# Sheet1.net
KiCad netlist of a schematic drawn in Altium Designer
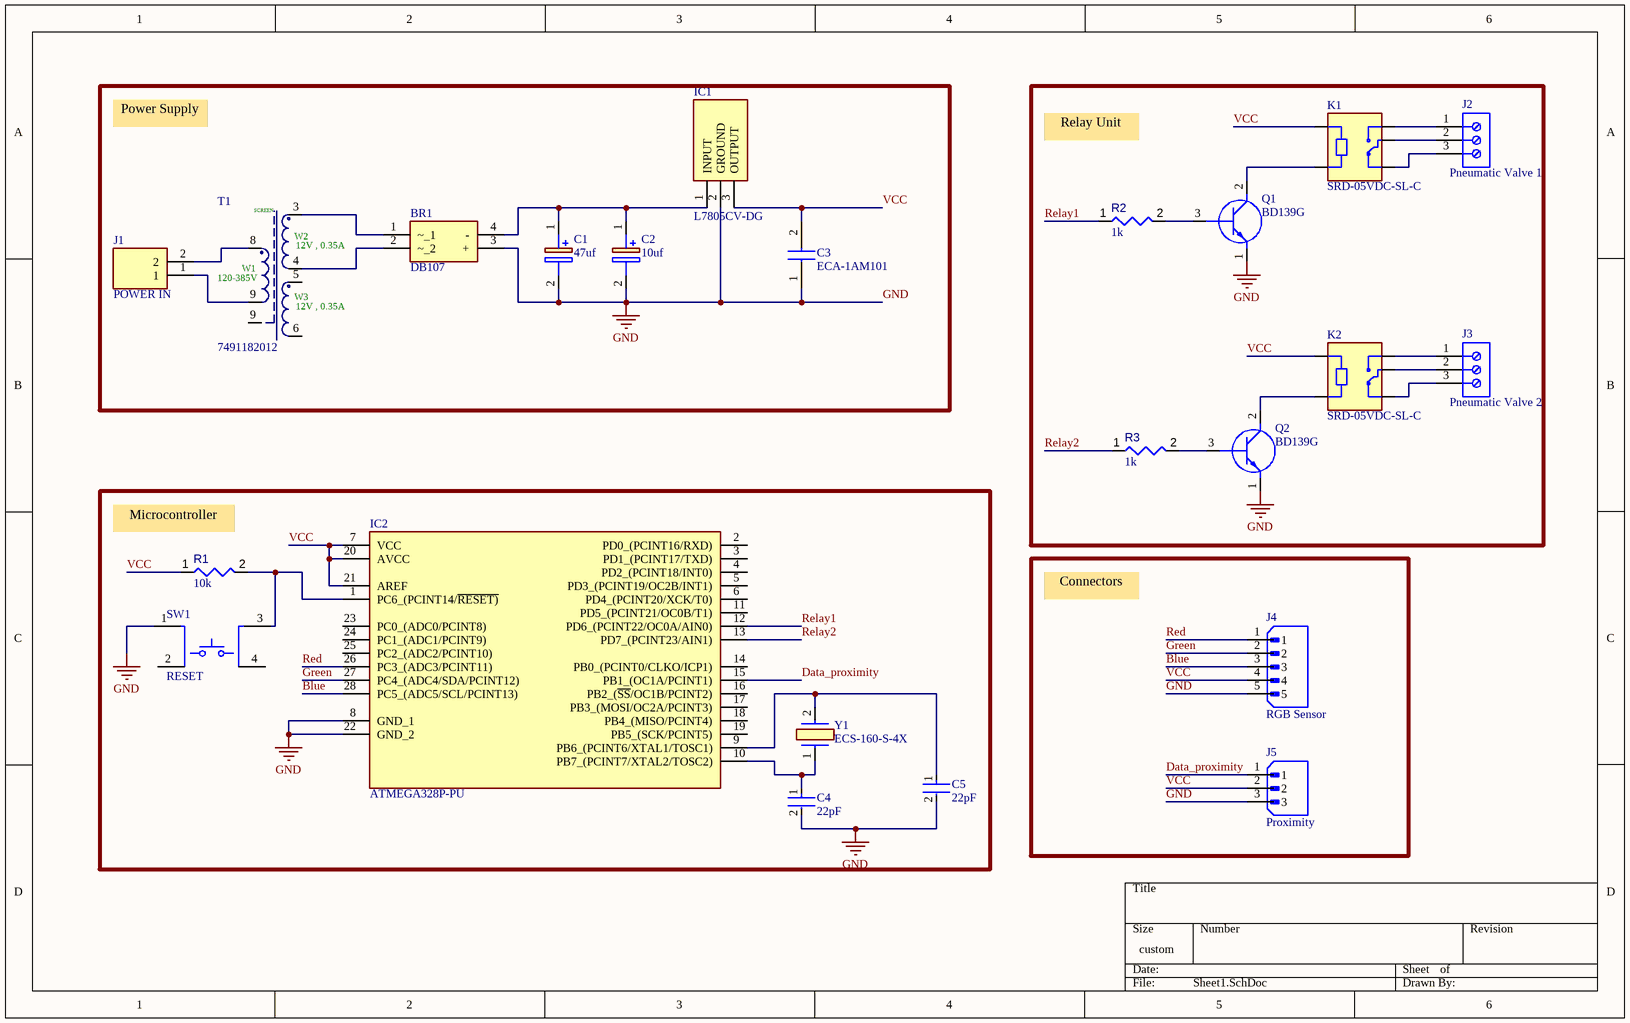
[diagram p0: Sheet1.SchDoc]

(export (version "E")
  (design (tool "Eeschema 10.0.6"))
  (components
    (comp (ref "BR1")
      (value "DB107")
      (footprint "SamacSys:DIP825W50P510L830H340Q4N")
      (description "Bridge Rectifier")
      (fields (field (name "MOUSER PART NUMBER") "583-DB107"))
      (libsource (lib "*") (part "DB107"))
    )
    (comp (ref "C1")
      (value "47uf")
      (footprint "SamacSys:CAPPRD250W55D630H1220")
      (description "Capacitor Polarised")
      (fields
        (field (name "MANUFACTURER_PART_NUMBER") "ECE-A1EN470UB")
        (field (name "MOUSER PART NUMBER") "667-ECE-A1EN470UB")
      )
      (libsource (lib "*") (part "ECE-A1EN470UB"))
    )
    (comp (ref "C2")
      (value "10uf")
      (footprint "SamacSys:CAPPRD200W55D500H1200")
      (description "Capacitor Polarised")
      (fields
        (field (name "MANUFACTURER_PART_NUMBER") "ECA-1EM100")
        (field (name "MOUSER PART NUMBER") "667-ECA-1EM100")
      )
      (libsource (lib "*") (part "ECA-1EM100"))
    )
    (comp (ref "C3")
      (value "ECA-1AM101")
      (footprint "SamacSys:CAPPRD200W55D525H1200")
      (description "Capacitor")
      (fields (field (name "MOUSER PART NUMBER") "667-ECA-1AM101"))
      (libsource (lib "*") (part "ECA-1AM101"))
    )
    (comp (ref "C4")
      (value "22pF")
      (footprint "FP-RCE0DB-MFG")
      (description "Cap Ceramic 22pF 100V C0G ±5% Radial 2.5mm +125°C Ammo Pack")
      (fields (field (name "VOLTAGE") "100V") (field (name "TOLERANCE") "5%"))
      (libsource (lib "Altium Content Vault") (part "b4654b650e69147ec39a6b967a45e02"))
    )
    (comp (ref "C5")
      (value "22pF")
      (footprint "FP-RCE0DB-MFG")
      (description "Cap Ceramic 22pF 100V C0G ±5% Radial 2.5mm +125°C Ammo Pack")
      (fields (field (name "VOLTAGE") "100V") (field (name "TOLERANCE") "5%"))
      (libsource (lib "Altium Content Vault") (part "b4654b650e69147ec39a6b967a45e02"))
    )
    (comp (ref "IC1")
      (value "L7805CV-DG")
      (footprint "SamacSys:TO255P460X1020X2008-3P")
      (description "Integrated Circuit")
      (fields (field (name "MOUSER PART NUMBER") "511-L7805CV-DG"))
      (libsource (lib "*") (part "L7805CV-DG"))
    )
    (comp (ref "IC2")
      (value "ATMEGA328P-PU")
      (footprint "SamacSys:DIP794W53P254L3467H457Q28N")
      (description "Integrated Circuit")
      (fields (field (name "MOUSER PART NUMBER") "556-ATMEGA328P-PU"))
      (libsource (lib "*") (part "ATMEGA328P-PU"))
    )
    (comp (ref "J1")
      (value "POWER IN")
      (footprint "SamacSys:TB00250002BE")
      (description "Connector")
      (fields
        (field (name "MANUFACTURER_PART_NUMBER") "TB002-500-02BE")
        (field (name "MOUSER PART NUMBER") "490-TB002-500-02BE")
      )
      (libsource (lib "*") (part "TB002-500-02BE"))
    )
    (comp (ref "J2")
      (value "Pneumatic Valve 1")
      (footprint "691101710003")
      (fields (field (name "VOLTAGE") "250V"))
      (libsource (lib "Altium Content Vault") (part "TBL - 1R - 03P - Screw"))
    )
    (comp (ref "J3")
      (value "Pneumatic Valve 2")
      (footprint "691101710003")
      (fields (field (name "VOLTAGE") "250V"))
      (libsource (lib "Altium Content Vault") (part "TBL - 1R - 03P - Screw"))
    )
    (comp (ref "J4")
      (value "RGB Sensor")
      (footprint "JST_B5B-XH-A(LF)(SN)")
      (description "Connector Header Through Hole 5 position 0.098 (2.50mm)")
      (fields (field (name "MF") "JST Sales America Inc.") (field (name "MP") "B5B-XH-A(LF)(SN)"))
      (libsource (lib "B5B-XH-A_LF__SN_") (part "B5B-XH-A(LF)(SN)"))
    )
    (comp (ref "J5")
      (value "Proximity")
      (footprint "JST_B3B-XH-A (LF)(SN)")
      (description "Connector Header Through Hole 3 position 0.098 (2.50mm)")
      (fields (field (name "MF") "JST Sales America Inc.") (field (name "MP") "B3B-XH-A (LF)(SN)"))
      (libsource (lib "B3B-XH-A__LF__SN_") (part "B3B-XH-A_(LF)(SN)"))
    )
    (comp (ref "K1")
      (value "SRD-05VDC-SL-C")
      (footprint "RELAY_SRD-05VDC-SL-C")
      (fields (field (name "MF") "Songle Relay"))
      (libsource (lib "SRD-05VDC-SL-C") (part "SRD-05VDC-SL-C"))
    )
    (comp (ref "K2")
      (value "SRD-05VDC-SL-C")
      (footprint "RELAY_SRD-05VDC-SL-C")
      (fields (field (name "MF") "Songle Relay"))
      (libsource (lib "SRD-05VDC-SL-C") (part "SRD-05VDC-SL-C"))
    )
    (comp (ref "Q1")
      (value "BD139G")
      (footprint "SamacSys:TO229P300X760X1364-3P")
      (description "Transistor BJT NPN")
      (fields (field (name "MOUSER PART NUMBER") "863-BD139G"))
      (libsource (lib "*") (part "BD139G"))
    )
    (comp (ref "Q2")
      (value "BD139G")
      (footprint "SamacSys:TO229P300X760X1364-3P")
      (description "Transistor BJT NPN")
      (fields (field (name "MOUSER PART NUMBER") "863-BD139G"))
      (libsource (lib "*") (part "BD139G"))
    )
    (comp (ref "R1")
      (value "10k")
      (footprint "RESA60-630X240")
      (description "Axial Resistor, 10 KOhm, +/- 1%, 0.25 W, -55 to 155 degC, 2-Pin THD, RoHS, Bulk")
      (fields (field (name "TOLERANCE") "1%") (field (name "POWER") "250mW"))
      (libsource (lib "Nidula  Gunawardana") (part "RES-2"))
    )
    (comp (ref "R2")
      (value "1k")
      (footprint "RESA60-630X240")
      (description "Axial Resistor, 1 KOhm, +/- 1%, 250 mW, -55 to 155 degC, 2-Pin THD, RoHS, Bulk")
      (fields (field (name "TOLERANCE") "1%") (field (name "POWER") "250mW"))
      (libsource (lib "Nidula  Gunawardana") (part "RES-2"))
    )
    (comp (ref "R3")
      (value "1k")
      (footprint "RESA60-630X240")
      (description "Axial Resistor, 1 KOhm, +/- 1%, 250 mW, -55 to 155 degC, 2-Pin THD, RoHS, Bulk")
      (fields (field (name "TOLERANCE") "1%") (field (name "POWER") "250mW"))
      (libsource (lib "Nidula  Gunawardana") (part "RES-2"))
    )
    (comp (ref "SW1")
      (value "RESET")
      (footprint "FP-SKQBARA010-MFG")
      (description "SKQBARA010 Switch Tactile N.O. SPST Round Button PC Pins 0.05A 12VDC 1.57N Thru-Hole Automotive")
      (libsource (lib "Altium Content Vault") (part "e22b01984cfc11d83da275cd8cd0ddf"))
    )
    (comp (ref "T1")
      (value "7491182012")
      (footprint "EE16_7_4 (E16)")
      (description "Off-Line Transformer WE-UNIT , L=0.9mH")
      (fields (field (name "MANUFACTURER") "Wuerth Elektronik"))
      (libsource (lib "Altium Content Vault") (part "WE-7491182012"))
    )
    (comp (ref "Y1")
      (value "ECS-160-S-4X")
      (footprint "SamacSys:ECS160S4X")
      (description "Crystal or Oscillator")
      (fields (field (name "MOUSER PART NUMBER") "520-HCU1600-SX"))
      (libsource (lib "*") (part "ECS-160-S-4X"))
    )
  )
  (nets
    (net (code "1") (name "/Blue") (class "Default")
      (node (ref "IC2") (pin "28") (pinfunction "PC5_(ADC5/SCL/PCINT13)_28") (pintype "passive"))
      (node (ref "J4") (pin "3") (pinfunction "3_3") (pintype "passive"))
    )
    (net (code "2") (name "/Data_proximity") (class "Default")
      (node (ref "IC2") (pin "15") (pinfunction "PB1_(OC1A/PCINT1)_15") (pintype "passive"))
      (node (ref "J5") (pin "1") (pinfunction "1_1") (pintype "passive"))
    )
    (net (code "3") (name "/Green") (class "Default")
      (node (ref "IC2") (pin "27") (pinfunction "PC4_(ADC4/SDA/PCINT12)_27") (pintype "passive"))
      (node (ref "J4") (pin "2") (pinfunction "2_2") (pintype "passive"))
    )
    (net (code "4") (name "/Red") (class "Default")
      (node (ref "IC2") (pin "26") (pinfunction "PC3_(ADC3/PCINT11)_26") (pintype "passive"))
      (node (ref "J4") (pin "1") (pinfunction "1_1") (pintype "passive"))
    )
    (net (code "5") (name "/Relay1") (class "Default")
      (node (ref "IC2") (pin "12") (pinfunction "PD6_(PCINT22/OC0A/AIN0)_12") (pintype "passive"))
      (node (ref "R2") (pin "1") (pinfunction "1_1") (pintype "passive"))
    )
    (net (code "6") (name "/Relay2") (class "Default")
      (node (ref "IC2") (pin "13") (pinfunction "PD7_(PCINT23/AIN1)_13") (pintype "passive"))
      (node (ref "R3") (pin "1") (pinfunction "1_1") (pintype "passive"))
    )
    (net (code "7") (name "/VCC") (class "Default")
      (node (ref "C3") (pin "2") (pinfunction "-_2") (pintype "passive"))
      (node (ref "IC1") (pin "3") (pinfunction "OUTPUT_3") (pintype "passive"))
      (node (ref "IC2") (pin "20") (pinfunction "AVCC_20") (pintype "passive"))
      (node (ref "IC2") (pin "21") (pinfunction "AREF_21") (pintype "passive"))
      (node (ref "IC2") (pin "7") (pinfunction "VCC_7") (pintype "passive"))
      (node (ref "J4") (pin "4") (pinfunction "4_4") (pintype "passive"))
      (node (ref "J5") (pin "2") (pinfunction "2_2") (pintype "passive"))
      (node (ref "K1") (pin "A1") (pinfunction "A1_A1") (pintype "passive"))
      (node (ref "K2") (pin "A1") (pinfunction "A1_A1") (pintype "passive"))
      (node (ref "R1") (pin "1") (pinfunction "1_1") (pintype "passive"))
    )
    (net (code "8") (name "GND") (class "Default")
      (node (ref "BR1") (pin "3") (pinfunction "+_3") (pintype "passive"))
      (node (ref "C1") (pin "2") (pinfunction "-_2") (pintype "passive"))
      (node (ref "C2") (pin "2") (pinfunction "-_2") (pintype "passive"))
      (node (ref "C3") (pin "1") (pinfunction "+_1") (pintype "passive"))
      (node (ref "C4") (pin "2") (pinfunction "2_2") (pintype "passive"))
      (node (ref "C5") (pin "2") (pinfunction "2_2") (pintype "passive"))
      (node (ref "IC1") (pin "2") (pinfunction "GROUND_2") (pintype "passive"))
      (node (ref "IC2") (pin "22") (pinfunction "GND_2_22") (pintype "passive"))
      (node (ref "IC2") (pin "8") (pinfunction "GND_1_8") (pintype "passive"))
      (node (ref "J4") (pin "5") (pinfunction "5_5") (pintype "passive"))
      (node (ref "J5") (pin "3") (pinfunction "3_3") (pintype "passive"))
      (node (ref "Q1") (pin "1") (pinfunction "E_1") (pintype "passive"))
      (node (ref "Q2") (pin "1") (pinfunction "E_1") (pintype "passive"))
      (node (ref "SW1") (pin "1") (pinfunction "1_1") (pintype "passive"))
    )
    (net (code "9") (name "Net-(BR1--)") (class "Default")
      (node (ref "BR1") (pin "4") (pinfunction "-_4") (pintype "passive"))
      (node (ref "C1") (pin "1") (pinfunction "+_1") (pintype "passive"))
      (node (ref "C2") (pin "1") (pinfunction "+_1") (pintype "passive"))
      (node (ref "IC1") (pin "1") (pinfunction "INPUT_1") (pintype "passive"))
    )
    (net (code "10") (name "Net-(BR1-~_1)") (class "Default")
      (node (ref "BR1") (pin "1") (pinfunction "~_1_1") (pintype "passive"))
      (node (ref "T1") (pin "3") (pinfunction "3_3") (pintype "passive"))
    )
    (net (code "11") (name "Net-(BR1-~_2)") (class "Default")
      (node (ref "BR1") (pin "2") (pinfunction "~_2_2") (pintype "passive"))
      (node (ref "T1") (pin "4") (pinfunction "4_4") (pintype "passive"))
    )
    (net (code "12") (name "Net-(IC2-PB6_(PCINT6{slash}XTAL1{slash}TOSC1))") (class "Default")
      (node (ref "C5") (pin "1") (pinfunction "1_1") (pintype "passive"))
      (node (ref "IC2") (pin "9") (pinfunction "PB6_(PCINT6/XTAL1/TOSC1)_9") (pintype "passive"))
      (node (ref "Y1") (pin "2") (pinfunction "2_2") (pintype "passive"))
    )
    (net (code "13") (name "Net-(IC2-PB7_(PCINT7{slash}XTAL2{slash}TOSC2))") (class "Default")
      (node (ref "C4") (pin "1") (pinfunction "1_1") (pintype "passive"))
      (node (ref "IC2") (pin "10") (pinfunction "PB7_(PCINT7/XTAL2/TOSC2)_10") (pintype "passive"))
      (node (ref "Y1") (pin "1") (pinfunction "1_1") (pintype "passive"))
    )
    (net (code "14") (name "Net-(IC2-PC6_(PCINT14{slash}~{RESET)})") (class "Default")
      (node (ref "IC2") (pin "1") (pinfunction "PC6_(PCINT14/~{RESET)}_1") (pintype "passive"))
      (node (ref "R1") (pin "2") (pinfunction "2_2") (pintype "passive"))
      (node (ref "SW1") (pin "3") (pinfunction "3_3") (pintype "passive"))
    )
    (net (code "15") (name "Net-(J1-Pad1)") (class "Default")
      (node (ref "J1") (pin "1") (pinfunction "1_1") (pintype "passive"))
      (node (ref "T1") (pin "9") (pinfunction "9_9") (pintype "passive"))
    )
    (net (code "16") (name "Net-(J1-Pad2)") (class "Default")
      (node (ref "J1") (pin "2") (pinfunction "2_2") (pintype "passive"))
      (node (ref "T1") (pin "8") (pinfunction "8_8") (pintype "passive"))
    )
    (net (code "17") (name "Net-(J2-Pad1)") (class "Default")
      (node (ref "J2") (pin "1") (pinfunction "1_1") (pintype "passive"))
      (node (ref "K1") (pin "NO") (pinfunction "NO_NO") (pintype "passive"))
    )
    (net (code "18") (name "Net-(J2-Pad2)") (class "Default")
      (node (ref "J2") (pin "2") (pinfunction "2_2") (pintype "passive"))
      (node (ref "K1") (pin "COM") (pinfunction "COM_COM") (pintype "passive"))
    )
    (net (code "19") (name "Net-(J2-Pad3)") (class "Default")
      (node (ref "J2") (pin "3") (pinfunction "3_3") (pintype "passive"))
      (node (ref "K1") (pin "NC") (pinfunction "NC_NC") (pintype "passive"))
    )
    (net (code "20") (name "Net-(J3-Pad1)") (class "Default")
      (node (ref "J3") (pin "1") (pinfunction "1_1") (pintype "passive"))
      (node (ref "K2") (pin "NO") (pinfunction "NO_NO") (pintype "passive"))
    )
    (net (code "21") (name "Net-(J3-Pad2)") (class "Default")
      (node (ref "J3") (pin "2") (pinfunction "2_2") (pintype "passive"))
      (node (ref "K2") (pin "COM") (pinfunction "COM_COM") (pintype "passive"))
    )
    (net (code "22") (name "Net-(J3-Pad3)") (class "Default")
      (node (ref "J3") (pin "3") (pinfunction "3_3") (pintype "passive"))
      (node (ref "K2") (pin "NC") (pinfunction "NC_NC") (pintype "passive"))
    )
    (net (code "23") (name "Net-(Q1-B)") (class "Default")
      (node (ref "Q1") (pin "3") (pinfunction "B_3") (pintype "passive"))
      (node (ref "R2") (pin "2") (pinfunction "2_2") (pintype "passive"))
    )
    (net (code "24") (name "Net-(Q1-C)") (class "Default")
      (node (ref "K1") (pin "A2") (pinfunction "A2_A2") (pintype "passive"))
      (node (ref "Q1") (pin "2") (pinfunction "C_2") (pintype "passive"))
    )
    (net (code "25") (name "Net-(Q2-B)") (class "Default")
      (node (ref "Q2") (pin "3") (pinfunction "B_3") (pintype "passive"))
      (node (ref "R3") (pin "2") (pinfunction "2_2") (pintype "passive"))
    )
    (net (code "26") (name "Net-(Q2-C)") (class "Default")
      (node (ref "K2") (pin "A2") (pinfunction "A2_A2") (pintype "passive"))
      (node (ref "Q2") (pin "2") (pinfunction "C_2") (pintype "passive"))
    )
    (net (code "27") (name "unconnected-(IC2-PB0_(PCINT0{slash}CLKO{slash}ICP1)-Pad14)") (class "Default")
      (node (ref "IC2") (pin "14") (pinfunction "PB0_(PCINT0/CLKO/ICP1)_14") (pintype "passive"))
    )
    (net (code "28") (name "unconnected-(IC2-PB2_(~{SS}{slash}OC1B{slash}PCINT2)-Pad16)") (class "Default")
      (node (ref "IC2") (pin "16") (pinfunction "PB2_(~{SS}/OC1B/PCINT2)_16") (pintype "passive"))
    )
    (net (code "29") (name "unconnected-(IC2-PB3_(MOSI{slash}OC2A{slash}PCINT3)-Pad17)") (class "Default")
      (node (ref "IC2") (pin "17") (pinfunction "PB3_(MOSI/OC2A/PCINT3)_17") (pintype "passive"))
    )
    (net (code "30") (name "unconnected-(IC2-PB4_(MISO{slash}PCINT4)-Pad18)") (class "Default")
      (node (ref "IC2") (pin "18") (pinfunction "PB4_(MISO/PCINT4)_18") (pintype "passive"))
    )
    (net (code "31") (name "unconnected-(IC2-PB5_(SCK{slash}PCINT5)-Pad19)") (class "Default")
      (node (ref "IC2") (pin "19") (pinfunction "PB5_(SCK/PCINT5)_19") (pintype "passive"))
    )
    (net (code "32") (name "unconnected-(IC2-PC0_(ADC0{slash}PCINT8)-Pad23)") (class "Default")
      (node (ref "IC2") (pin "23") (pinfunction "PC0_(ADC0/PCINT8)_23") (pintype "passive"))
    )
    (net (code "33") (name "unconnected-(IC2-PC1_(ADC1{slash}PCINT9)-Pad24)") (class "Default")
      (node (ref "IC2") (pin "24") (pinfunction "PC1_(ADC1/PCINT9)_24") (pintype "passive"))
    )
    (net (code "34") (name "unconnected-(IC2-PC2_(ADC2{slash}PCINT10)-Pad25)") (class "Default")
      (node (ref "IC2") (pin "25") (pinfunction "PC2_(ADC2/PCINT10)_25") (pintype "passive"))
    )
    (net (code "35") (name "unconnected-(IC2-PD0_(PCINT16{slash}RXD)-Pad2)") (class "Default")
      (node (ref "IC2") (pin "2") (pinfunction "PD0_(PCINT16/RXD)_2") (pintype "passive"))
    )
    (net (code "36") (name "unconnected-(IC2-PD1_(PCINT17{slash}TXD)-Pad3)") (class "Default")
      (node (ref "IC2") (pin "3") (pinfunction "PD1_(PCINT17/TXD)_3") (pintype "passive"))
    )
    (net (code "37") (name "unconnected-(IC2-PD2_(PCINT18{slash}INT0)-Pad4)") (class "Default")
      (node (ref "IC2") (pin "4") (pinfunction "PD2_(PCINT18/INT0)_4") (pintype "passive"))
    )
    (net (code "38") (name "unconnected-(IC2-PD3_(PCINT19{slash}OC2B{slash}INT1)-Pad5)") (class "Default")
      (node (ref "IC2") (pin "5") (pinfunction "PD3_(PCINT19/OC2B/INT1)_5") (pintype "passive"))
    )
    (net (code "39") (name "unconnected-(IC2-PD4_(PCINT20{slash}XCK{slash}T0)-Pad6)") (class "Default")
      (node (ref "IC2") (pin "6") (pinfunction "PD4_(PCINT20/XCK/T0)_6") (pintype "passive"))
    )
    (net (code "40") (name "unconnected-(IC2-PD5_(PCINT21{slash}OC0B{slash}T1)-Pad11)") (class "Default")
      (node (ref "IC2") (pin "11") (pinfunction "PD5_(PCINT21/OC0B/T1)_11") (pintype "passive"))
    )
    (net (code "41") (name "unconnected-(SW1-Pad2)") (class "Default")
      (node (ref "SW1") (pin "2") (pinfunction "2_2") (pintype "passive"))
    )
    (net (code "42") (name "unconnected-(SW1-Pad4)") (class "Default")
      (node (ref "SW1") (pin "4") (pinfunction "4_4") (pintype "passive"))
    )
    (net (code "43") (name "unconnected-(T1-Pad5)") (class "Default")
      (node (ref "T1") (pin "5") (pinfunction "5_5") (pintype "passive"))
    )
    (net (code "44") (name "unconnected-(T1-Pad6)") (class "Default")
      (node (ref "T1") (pin "6") (pinfunction "6_6") (pintype "passive"))
    )
    (net (code "45") (name "unconnected-(T1-Pad9)") (class "Default")
      (node (ref "T1") (pin "9") (pinfunction "9_9") (pintype "passive"))
    )
  )
)
